# AnchorUWB.net
KiCad netlist of a schematic drawn in Altium Designer
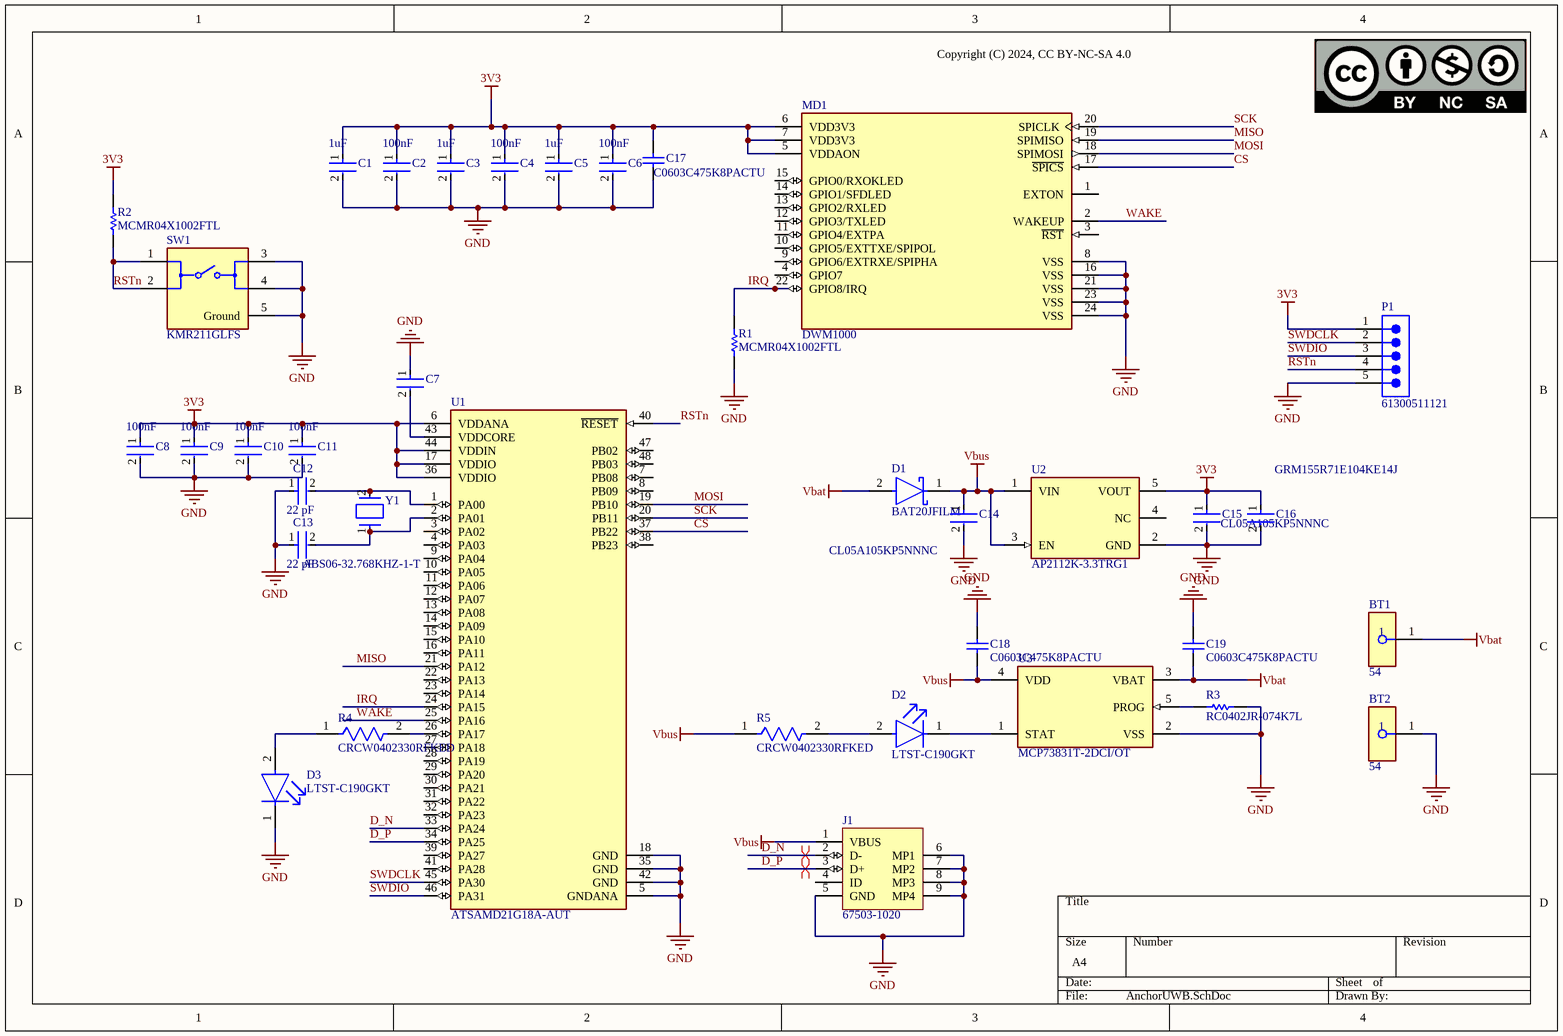
[diagram p0: AnchorUWB.SchDoc]

(export (version "E")
  (design (tool "Eeschema 10.0.6"))
  (components
    (comp (ref "BT1")
      (value "54")
      (footprint "FP-54-MFG")
      (description "BATTERY CONTACT CLP 18650 PC PIN")
      (libsource (lib "Altium Content Vault") (part "98815daf2f2c152b0c43f5ab9800df6"))
    )
    (comp (ref "BT2")
      (value "54")
      (footprint "FP-54-MFG")
      (description "BATTERY CONTACT CLP 18650 PC PIN")
      (libsource (lib "Altium Content Vault") (part "98815daf2f2c152b0c43f5ab9800df6"))
    )
    (comp (ref "C1")
      (value "CL05A105KP5NNNC")
      (footprint "FP-CL511-IPC_C")
      (description "Cap Ceramic 1uF 10V X5R ±10% SMD 0402 +85°C Paper T/R")
      (fields (field (name "CAPACITANCE") "1uF") (field (name "TOLERANCE") "10%"))
      (libsource (lib "Altium Content Vault") (part "b4654b650e69147ec39a6b967a45e02"))
    )
    (comp (ref "C2")
      (value "GRM155R71E104KE14J")
      (footprint "FP-GRM155-0_05-IPC_C")
      (description "Chip Multilayer Ceramic Capacitors for General Purpose, 0402, 0.10uF, X7R, 15%, 10%, 25V")
      (fields (field (name "CAPACITANCE") "100nF") (field (name "TOLERANCE") "10%"))
      (libsource (lib "Altium Content Vault") (part "02cd4be3c70576c341d710602a673aa"))
    )
    (comp (ref "C3")
      (value "CL05A105KP5NNNC")
      (footprint "FP-CL511-IPC_C")
      (description "Cap Ceramic 1uF 10V X5R ±10% SMD 0402 +85°C Paper T/R")
      (fields (field (name "CAPACITANCE") "1uF") (field (name "TOLERANCE") "10%"))
      (libsource (lib "Altium Content Vault") (part "b4654b650e69147ec39a6b967a45e02"))
    )
    (comp (ref "C4")
      (value "GRM155R71E104KE14J")
      (footprint "FP-GRM155-0_05-IPC_C")
      (description "Chip Multilayer Ceramic Capacitors for General Purpose, 0402, 0.10uF, X7R, 15%, 10%, 25V")
      (fields (field (name "CAPACITANCE") "100nF") (field (name "TOLERANCE") "10%"))
      (libsource (lib "Altium Content Vault") (part "02cd4be3c70576c341d710602a673aa"))
    )
    (comp (ref "C5")
      (value "CL05A105KP5NNNC")
      (footprint "FP-CL511-IPC_C")
      (description "Cap Ceramic 1uF 10V X5R ±10% SMD 0402 +85°C Paper T/R")
      (fields (field (name "CAPACITANCE") "1uF") (field (name "TOLERANCE") "10%"))
      (libsource (lib "Altium Content Vault") (part "b4654b650e69147ec39a6b967a45e02"))
    )
    (comp (ref "C6")
      (value "GRM155R71E104KE14J")
      (footprint "FP-GRM155-0_05-IPC_C")
      (description "Chip Multilayer Ceramic Capacitors for General Purpose, 0402, 0.10uF, X7R, 15%, 10%, 25V")
      (fields (field (name "CAPACITANCE") "100nF") (field (name "TOLERANCE") "10%"))
      (libsource (lib "Altium Content Vault") (part "02cd4be3c70576c341d710602a673aa"))
    )
    (comp (ref "C7")
      (value "CL05A105KP5NNNC")
      (footprint "FP-CL511-IPC_C")
      (description "Cap Ceramic 1uF 10V X5R ±10% SMD 0402 +85°C Paper T/R")
      (fields (field (name "TOLERANCE") "10%"))
      (libsource (lib "Altium Content Vault") (part "b4654b650e69147ec39a6b967a45e02"))
    )
    (comp (ref "C8")
      (value "GRM155R71E104KE14J")
      (footprint "FP-GRM155-0_05-IPC_C")
      (description "Chip Multilayer Ceramic Capacitors for General Purpose, 0402, 0.10uF, X7R, 15%, 10%, 25V")
      (fields (field (name "CAPACITANCE") "100nF") (field (name "TOLERANCE") "10%"))
      (libsource (lib "Altium Content Vault") (part "02cd4be3c70576c341d710602a673aa"))
    )
    (comp (ref "C9")
      (value "GRM155R71E104KE14J")
      (footprint "FP-GRM155-0_05-IPC_C")
      (description "Chip Multilayer Ceramic Capacitors for General Purpose, 0402, 0.10uF, X7R, 15%, 10%, 25V")
      (fields (field (name "CAPACITANCE") "100nF") (field (name "TOLERANCE") "10%"))
      (libsource (lib "Altium Content Vault") (part "02cd4be3c70576c341d710602a673aa"))
    )
    (comp (ref "C10")
      (value "GRM155R71E104KE14J")
      (footprint "FP-GRM155-0_05-IPC_C")
      (description "Chip Multilayer Ceramic Capacitors for General Purpose, 0402, 0.10uF, X7R, 15%, 10%, 25V")
      (fields (field (name "CAPACITANCE") "100nF") (field (name "TOLERANCE") "10%"))
      (libsource (lib "Altium Content Vault") (part "02cd4be3c70576c341d710602a673aa"))
    )
    (comp (ref "C11")
      (value "GRM155R71E104KE14J")
      (footprint "FP-GRM155-0_05-IPC_C")
      (description "Chip Multilayer Ceramic Capacitors for General Purpose, 0402, 0.10uF, X7R, 15%, 10%, 25V")
      (fields (field (name "CAPACITANCE") "100nF") (field (name "TOLERANCE") "10%"))
      (libsource (lib "Altium Content Vault") (part "02cd4be3c70576c341d710602a673aa"))
    )
    (comp (ref "C12")
      (value "C0402C220K5GACTU")
      (footprint "FP-C0402-BB-MFG")
      (description "CAP CER 22PF 50V 10% NP0 0402")
      (fields
        (field (name "OCTOPART") "https://octopart.com/c0402c220k5gactu-kemet-9144192")
        (field (name "CAPACITANCE") "22 pF")
        (field (name "TOLERANCE") "0.1")
      )
      (libsource (lib "Altium Content Vault") (part "b4654b650e69147ec39a6b967a45e02"))
    )
    (comp (ref "C13")
      (value "C0402C220K5GACTU")
      (footprint "FP-C0402-BB-MFG")
      (description "CAP CER 22PF 50V 10% NP0 0402")
      (fields
        (field (name "OCTOPART") "https://octopart.com/c0402c220k5gactu-kemet-9144192")
        (field (name "CAPACITANCE") "22 pF")
        (field (name "TOLERANCE") "0.1")
      )
      (libsource (lib "Altium Content Vault") (part "b4654b650e69147ec39a6b967a45e02"))
    )
    (comp (ref "C14")
      (value "CL05A105KP5NNNC")
      (footprint "FP-CL511-IPC_C")
      (description "Cap Ceramic 1uF 10V X5R ±10% SMD 0402 +85°C Paper T/R")
      (fields (field (name "TOLERANCE") "10%"))
      (libsource (lib "Altium Content Vault") (part "b4654b650e69147ec39a6b967a45e02"))
    )
    (comp (ref "C15")
      (value "CL05A105KP5NNNC")
      (footprint "FP-CL511-IPC_C")
      (description "Cap Ceramic 1uF 10V X5R ±10% SMD 0402 +85°C Paper T/R")
      (fields (field (name "TOLERANCE") "10%"))
      (libsource (lib "Altium Content Vault") (part "b4654b650e69147ec39a6b967a45e02"))
    )
    (comp (ref "C16")
      (value "GRM155R71E104KE14J")
      (footprint "FP-GRM155-0_05-IPC_C")
      (description "Chip Multilayer Ceramic Capacitors for General Purpose, 0402, 0.10uF, X7R, 15%, 10%, 25V")
      (fields (field (name "TOLERANCE") "10%"))
      (libsource (lib "Altium Content Vault") (part "02cd4be3c70576c341d710602a673aa"))
    )
    (comp (ref "C17")
      (value "C0603C475K8PACTU")
      (footprint "CAPC1608X87X35NL15T15")
      (fields (field (name "PART NUMBER") "C0603C475K8PACTU") (field (name "MANUFACTURER") "Kemet"))
      (libsource (lib "Altium Content Vault") (part "CAP"))
    )
    (comp (ref "C18")
      (value "C0603C475K8PACTU")
      (footprint "CAPC1608X87X35NL15T15")
      (fields (field (name "MANUFACTURER") "Kemet"))
      (libsource (lib "Altium Content Vault") (part "CAP"))
    )
    (comp (ref "C19")
      (value "C0603C475K8PACTU")
      (footprint "CAPC1608X87X35NL15T15")
      (fields (field (name "MANUFACTURER") "Kemet"))
      (libsource (lib "Altium Content Vault") (part "CAP"))
    )
    (comp (ref "D1")
      (value "BAT20JFILM")
      (footprint "FP-BAT20JFILM-MFG")
      (description "DIODE SCHOTTKY 23V 1A SOD323")
      (libsource (lib "Altium Content Vault") (part "fefb30dabb5d097ae2f038500735429"))
    )
    (comp (ref "D2")
      (value "LTST-C190GKT")
      (footprint "FP-LTST-C190GKT-MFG")
      (description "LED GREEN CLEAR CHIP SMD")
      (fields (field (name "VOLTAGE") "2V"))
      (libsource (lib "Altium Content Vault") (part "8706943c75ba83719d021d2fdc84c58"))
    )
    (comp (ref "D3")
      (value "LTST-C190GKT")
      (footprint "FP-LTST-C190GKT-MFG")
      (description "LED GREEN CLEAR CHIP SMD")
      (fields (field (name "VOLTAGE") "2V"))
      (libsource (lib "Altium Content Vault") (part "8706943c75ba83719d021d2fdc84c58"))
    )
    (comp (ref "J1")
      (value "67503-1020")
      (footprint "MOLX-67503-1020_V")
      (description "USB, MINI, SMD, RA KME04-USBMU03A01")
      (fields (field (name "MANUFACTURER") "Molex"))
      (libsource (lib "Altium Content Vault") (part "MOLX-67503-1020"))
    )
    (comp (ref "MD1")
      (value "DWM1000")
      (footprint "FP-DWM1000-MFG")
      (description "RX TXRX MODULE 802.15.4 CHIP SMD")
      (libsource (lib "Altium Content Vault") (part "f696d20320cfac42d99354fdc9dc59a"))
    )
    (comp (ref "P1")
      (value "61300511121")
      (footprint "61300511121")
      (libsource (lib "Altium Content Vault") (part "Header_Male_1R_05P"))
    )
    (comp (ref "R1")
      (value "MCMR04X1002FTL")
      (footprint "RESC1005X40X25NL05T10")
      (fields (field (name "MANUFACTURER") "Multicomp"))
      (libsource (lib "Altium Content Vault") (part "RES"))
    )
    (comp (ref "R2")
      (value "MCMR04X1002FTL")
      (footprint "RESC1005X40X25NL05T10")
      (fields (field (name "MANUFACTURER") "Multicomp"))
      (libsource (lib "Altium Content Vault") (part "RES"))
    )
    (comp (ref "R3")
      (value "RC0402JR-074K7L")
      (footprint "RESC1005X40X25LL05T10")
      (fields (field (name "MANUFACTURER") "Yageo / Phycomp"))
      (libsource (lib "Altium Content Vault") (part "RES"))
    )
    (comp (ref "R4")
      (value "CRCW0402330RFKED")
      (footprint "FP-CRCW0402-e3-MFG")
      (description "RES Thick Film, 330Ω, 1%, 0.063W, 100ppm/°C, 0402")
      (fields (field (name "TOLERANCE") "1%"))
      (libsource (lib "Altium Content Vault") (part "1029c3af85768c4190bb7ad29bc67b5"))
    )
    (comp (ref "R5")
      (value "CRCW0402330RFKED")
      (footprint "FP-CRCW0402-e3-MFG")
      (description "RES Thick Film, 330Ω, 1%, 0.063W, 100ppm/°C, 0402")
      (fields (field (name "TOLERANCE") "1%"))
      (libsource (lib "Altium Content Vault") (part "1029c3af85768c4190bb7ad29bc67b5"))
    )
    (comp (ref "SW1")
      (value "KMR211GLFS")
      (footprint "FP-KMR211GLFS-MFG")
      (description "SWITCH TACTILE SPST-NO 0.05A 32V")
      (libsource (lib "Altium Content Vault") (part "99988cc0f9d3d39bd794ae22da860e5"))
    )
    (comp (ref "U1")
      (value "ATSAMD21G18A-AUT")
      (footprint "FP-MC-MFG")
      (description "IC MCU 32BIT 256KB FLASH 48TQFP")
      (libsource (lib "Altium Content Vault") (part "cb504b5d9f62c9ff840dfafac9e9c83"))
    )
    (comp (ref "U2")
      (value "AP2112K-3.3TRG1")
      (footprint "FP-SOT25-IPC_A")
      (description "IC REG LINEAR 3.3V 600MA SOT25")
      (libsource (lib "Altium Content Vault") (part "c8ab751aee5229183125ab046a11caa"))
    )
    (comp (ref "U3")
      (value "MCP73831T-2DCI/OT")
      (footprint "FP-C04-091-OT-IPC_B")
      (description "IC CONTROLLR LI-ION 4.2V SOT23-5")
      (libsource (lib "Altium Content Vault") (part "61f5a3bb3429d9e0caadea342aa3b19"))
    )
    (comp (ref "Y1")
      (value "ABS06-32.768KHZ-1-T")
      (footprint "FP-ABS06-MFG")
      (description "CRYSTAL 32.7680KHZ 12.5PF SMD")
      (fields (field (name "TOLERANCE") "10ppm"))
      (libsource (lib "Altium Content Vault") (part "c23a69dc6c9e2f18f2079038eb95dd1"))
    )
  )
  (nets
    (net (code "1") (name "/CS") (class "Default")
      (node (ref "MD1") (pin "17") (pinfunction "~{SPICS}_17") (pintype "input"))
      (node (ref "U1") (pin "37") (pinfunction "PB22_37") (pintype "bidirectional"))
    )
    (net (code "2") (name "/D_N") (class "Default")
      (node (ref "J1") (pin "2") (pinfunction "D-_2") (pintype "bidirectional"))
      (node (ref "U1") (pin "33") (pinfunction "PA24_33") (pintype "bidirectional"))
    )
    (net (code "3") (name "/D_P") (class "Default")
      (node (ref "J1") (pin "3") (pinfunction "D+_3") (pintype "bidirectional"))
      (node (ref "U1") (pin "34") (pinfunction "PA25_34") (pintype "bidirectional"))
    )
    (net (code "4") (name "/IRQ") (class "Default")
      (node (ref "MD1") (pin "22") (pinfunction "GPIO8/IRQ_22") (pintype "bidirectional"))
      (node (ref "R1") (pin "2") (pinfunction "2_2") (pintype "passive"))
      (node (ref "U1") (pin "24") (pinfunction "PA15_24") (pintype "bidirectional"))
    )
    (net (code "5") (name "/MISO") (class "Default")
      (node (ref "MD1") (pin "19") (pinfunction "SPIMISO_19") (pintype "input"))
      (node (ref "U1") (pin "21") (pinfunction "PA12_21") (pintype "bidirectional"))
    )
    (net (code "6") (name "/MOSI") (class "Default")
      (node (ref "MD1") (pin "18") (pinfunction "SPIMOSI_18") (pintype "output"))
      (node (ref "U1") (pin "19") (pinfunction "PB10_19") (pintype "bidirectional"))
    )
    (net (code "7") (name "/RSTn") (class "Default")
      (node (ref "P1") (pin "4") (pinfunction "4_4") (pintype "passive"))
      (node (ref "R2") (pin "1") (pinfunction "1_1") (pintype "passive"))
      (node (ref "SW1") (pin "1") (pinfunction "1_1") (pintype "passive"))
      (node (ref "SW1") (pin "2") (pinfunction "2_2") (pintype "passive"))
      (node (ref "U1") (pin "40") (pinfunction "~{RESET}_40") (pintype "input"))
    )
    (net (code "8") (name "/SCK") (class "Default")
      (node (ref "MD1") (pin "20") (pinfunction "SPICLK_20") (pintype "input"))
      (node (ref "U1") (pin "20") (pinfunction "PB11_20") (pintype "bidirectional"))
    )
    (net (code "9") (name "/SWDCLK") (class "Default")
      (node (ref "P1") (pin "2") (pinfunction "2_2") (pintype "passive"))
      (node (ref "U1") (pin "45") (pinfunction "PA30_45") (pintype "bidirectional"))
    )
    (net (code "10") (name "/SWDIO") (class "Default")
      (node (ref "P1") (pin "3") (pinfunction "3_3") (pintype "passive"))
      (node (ref "U1") (pin "46") (pinfunction "PA31_46") (pintype "bidirectional"))
    )
    (net (code "11") (name "/WAKE") (class "Default")
      (node (ref "MD1") (pin "2") (pinfunction "WAKEUP_2") (pintype "passive"))
      (node (ref "U1") (pin "25") (pinfunction "PA16_25") (pintype "bidirectional"))
    )
    (net (code "12") (name "3V3") (class "Default")
      (node (ref "C1") (pin "1") (pinfunction "1_1") (pintype "passive"))
      (node (ref "C10") (pin "1") (pinfunction "1_1") (pintype "passive"))
      (node (ref "C11") (pin "1") (pinfunction "1_1") (pintype "passive"))
      (node (ref "C15") (pin "1") (pinfunction "1_1") (pintype "passive"))
      (node (ref "C16") (pin "1") (pinfunction "1_1") (pintype "passive"))
      (node (ref "C17") (pin "2") (pinfunction "2_2") (pintype "passive"))
      (node (ref "C2") (pin "1") (pinfunction "1_1") (pintype "passive"))
      (node (ref "C3") (pin "1") (pinfunction "1_1") (pintype "passive"))
      (node (ref "C4") (pin "1") (pinfunction "1_1") (pintype "passive"))
      (node (ref "C5") (pin "1") (pinfunction "1_1") (pintype "passive"))
      (node (ref "C6") (pin "1") (pinfunction "1_1") (pintype "passive"))
      (node (ref "C8") (pin "1") (pinfunction "1_1") (pintype "passive"))
      (node (ref "C9") (pin "1") (pinfunction "1_1") (pintype "passive"))
      (node (ref "MD1") (pin "5") (pinfunction "VDDAON_5") (pintype "power_in"))
      (node (ref "MD1") (pin "6") (pinfunction "VDD3V3_6") (pintype "power_in"))
      (node (ref "MD1") (pin "7") (pinfunction "VDD3V3_7") (pintype "power_in"))
      (node (ref "P1") (pin "1") (pinfunction "1_1") (pintype "passive"))
      (node (ref "R2") (pin "2") (pinfunction "2_2") (pintype "passive"))
      (node (ref "U1") (pin "17") (pinfunction "VDDIO_17") (pintype "power_in"))
      (node (ref "U1") (pin "36") (pinfunction "VDDIO_36") (pintype "power_in"))
      (node (ref "U1") (pin "44") (pinfunction "VDDIN_44") (pintype "power_in"))
      (node (ref "U1") (pin "6") (pinfunction "VDDANA_6") (pintype "power_in"))
      (node (ref "U2") (pin "5") (pinfunction "VOUT_5") (pintype "power_in"))
    )
    (net (code "13") (name "GND") (class "Default")
      (node (ref "BT2") (pin "1") (pinfunction "1_1") (pintype "power_in"))
      (node (ref "C1") (pin "2") (pinfunction "2_2") (pintype "passive"))
      (node (ref "C10") (pin "2") (pinfunction "2_2") (pintype "passive"))
      (node (ref "C11") (pin "2") (pinfunction "2_2") (pintype "passive"))
      (node (ref "C12") (pin "1") (pinfunction "1_1") (pintype "passive"))
      (node (ref "C13") (pin "1") (pinfunction "1_1") (pintype "passive"))
      (node (ref "C14") (pin "2") (pinfunction "2_2") (pintype "passive"))
      (node (ref "C15") (pin "2") (pinfunction "2_2") (pintype "passive"))
      (node (ref "C16") (pin "2") (pinfunction "2_2") (pintype "passive"))
      (node (ref "C17") (pin "1") (pinfunction "1_1") (pintype "passive"))
      (node (ref "C18") (pin "2") (pinfunction "2_2") (pintype "passive"))
      (node (ref "C19") (pin "2") (pinfunction "2_2") (pintype "passive"))
      (node (ref "C2") (pin "2") (pinfunction "2_2") (pintype "passive"))
      (node (ref "C3") (pin "2") (pinfunction "2_2") (pintype "passive"))
      (node (ref "C4") (pin "2") (pinfunction "2_2") (pintype "passive"))
      (node (ref "C5") (pin "2") (pinfunction "2_2") (pintype "passive"))
      (node (ref "C6") (pin "2") (pinfunction "2_2") (pintype "passive"))
      (node (ref "C7") (pin "1") (pinfunction "1_1") (pintype "passive"))
      (node (ref "C8") (pin "2") (pinfunction "2_2") (pintype "passive"))
      (node (ref "C9") (pin "2") (pinfunction "2_2") (pintype "passive"))
      (node (ref "D3") (pin "1") (pinfunction "C_1") (pintype "passive"))
      (node (ref "J1") (pin "5") (pinfunction "GND_5") (pintype "power_in"))
      (node (ref "J1") (pin "6") (pinfunction "MP1_6") (pintype "passive"))
      (node (ref "J1") (pin "7") (pinfunction "MP2_7") (pintype "passive"))
      (node (ref "J1") (pin "8") (pinfunction "MP3_8") (pintype "passive"))
      (node (ref "J1") (pin "9") (pinfunction "MP4_9") (pintype "passive"))
      (node (ref "MD1") (pin "16") (pinfunction "VSS_16") (pintype "power_in"))
      (node (ref "MD1") (pin "21") (pinfunction "VSS_21") (pintype "power_in"))
      (node (ref "MD1") (pin "23") (pinfunction "VSS_23") (pintype "power_in"))
      (node (ref "MD1") (pin "24") (pinfunction "VSS_24") (pintype "power_in"))
      (node (ref "MD1") (pin "8") (pinfunction "VSS_8") (pintype "power_in"))
      (node (ref "P1") (pin "5") (pinfunction "5_5") (pintype "passive"))
      (node (ref "R1") (pin "1") (pinfunction "1_1") (pintype "passive"))
      (node (ref "R3") (pin "2") (pinfunction "2_2") (pintype "passive"))
      (node (ref "SW1") (pin "3") (pinfunction "3_3") (pintype "passive"))
      (node (ref "SW1") (pin "4") (pinfunction "4_4") (pintype "passive"))
      (node (ref "SW1") (pin "5") (pinfunction "Ground_5") (pintype "power_in"))
      (node (ref "U1") (pin "18") (pinfunction "GND_18") (pintype "power_in"))
      (node (ref "U1") (pin "35") (pinfunction "GND_35") (pintype "power_in"))
      (node (ref "U1") (pin "42") (pinfunction "GND_42") (pintype "power_in"))
      (node (ref "U1") (pin "5") (pinfunction "GNDANA_5") (pintype "power_in"))
      (node (ref "U2") (pin "2") (pinfunction "GND_2") (pintype "power_in"))
      (node (ref "U3") (pin "2") (pinfunction "VSS_2") (pintype "power_in"))
    )
    (net (code "14") (name "Net-(D2-A)") (class "Default")
      (node (ref "D2") (pin "2") (pinfunction "A_2") (pintype "passive"))
      (node (ref "R5") (pin "2") (pinfunction "2_2") (pintype "passive"))
    )
    (net (code "15") (name "Net-(D2-C)") (class "Default")
      (node (ref "D2") (pin "1") (pinfunction "C_1") (pintype "passive"))
      (node (ref "U3") (pin "1") (pinfunction "STAT_1") (pintype "passive"))
    )
    (net (code "16") (name "Net-(D3-A)") (class "Default")
      (node (ref "D3") (pin "2") (pinfunction "A_2") (pintype "passive"))
      (node (ref "R4") (pin "1") (pinfunction "1_1") (pintype "passive"))
    )
    (net (code "17") (name "Net-(U1-PA00)") (class "Default")
      (node (ref "C12") (pin "2") (pinfunction "2_2") (pintype "passive"))
      (node (ref "U1") (pin "1") (pinfunction "PA00_1") (pintype "bidirectional"))
      (node (ref "Y1") (pin "2") (pinfunction "2_2") (pintype "passive"))
    )
    (net (code "18") (name "Net-(U1-PA01)") (class "Default")
      (node (ref "C13") (pin "2") (pinfunction "2_2") (pintype "passive"))
      (node (ref "U1") (pin "2") (pinfunction "PA01_2") (pintype "bidirectional"))
      (node (ref "Y1") (pin "1") (pinfunction "1_1") (pintype "passive"))
    )
    (net (code "19") (name "Net-(U1-PA17)") (class "Default")
      (node (ref "R4") (pin "2") (pinfunction "2_2") (pintype "passive"))
      (node (ref "U1") (pin "26") (pinfunction "PA17_26") (pintype "bidirectional"))
    )
    (net (code "20") (name "Net-(U1-VDDCORE)") (class "Default")
      (node (ref "C7") (pin "2") (pinfunction "2_2") (pintype "passive"))
      (node (ref "U1") (pin "43") (pinfunction "VDDCORE_43") (pintype "power_in"))
    )
    (net (code "21") (name "Net-(U3-PROG)") (class "Default")
      (node (ref "R3") (pin "1") (pinfunction "1_1") (pintype "passive"))
      (node (ref "U3") (pin "5") (pinfunction "PROG_5") (pintype "input"))
    )
    (net (code "22") (name "Vbat") (class "Default")
      (node (ref "BT1") (pin "1") (pinfunction "1_1") (pintype "power_in"))
      (node (ref "C19") (pin "1") (pinfunction "1_1") (pintype "passive"))
      (node (ref "D1") (pin "2") (pinfunction "A_2") (pintype "passive"))
      (node (ref "U3") (pin "3") (pinfunction "VBAT_3") (pintype "power_in"))
    )
    (net (code "23") (name "Vbus") (class "Default")
      (node (ref "C14") (pin "1") (pinfunction "1_1") (pintype "passive"))
      (node (ref "C18") (pin "1") (pinfunction "1_1") (pintype "passive"))
      (node (ref "D1") (pin "1") (pinfunction "K_1") (pintype "passive"))
      (node (ref "J1") (pin "1") (pinfunction "VBUS_1") (pintype "power_in"))
      (node (ref "R5") (pin "1") (pinfunction "1_1") (pintype "passive"))
      (node (ref "U2") (pin "1") (pinfunction "VIN_1") (pintype "power_in"))
      (node (ref "U2") (pin "3") (pinfunction "EN_3") (pintype "input"))
      (node (ref "U3") (pin "4") (pinfunction "VDD_4") (pintype "open_emitter"))
    )
    (net (code "24") (name "unconnected-(J1-ID-Pad4)") (class "Default")
      (node (ref "J1") (pin "4") (pinfunction "ID_4") (pintype "passive"))
    )
    (net (code "25") (name "unconnected-(MD1-EXTON-Pad1)") (class "Default")
      (node (ref "MD1") (pin "1") (pinfunction "EXTON_1") (pintype "passive"))
    )
    (net (code "26") (name "unconnected-(MD1-GPIO0{slash}RXOKLED-Pad15)") (class "Default")
      (node (ref "MD1") (pin "15") (pinfunction "GPIO0/RXOKLED_15") (pintype "bidirectional"))
    )
    (net (code "27") (name "unconnected-(MD1-GPIO1{slash}SFDLED-Pad14)") (class "Default")
      (node (ref "MD1") (pin "14") (pinfunction "GPIO1/SFDLED_14") (pintype "bidirectional"))
    )
    (net (code "28") (name "unconnected-(MD1-GPIO2{slash}RXLED-Pad13)") (class "Default")
      (node (ref "MD1") (pin "13") (pinfunction "GPIO2/RXLED_13") (pintype "bidirectional"))
    )
    (net (code "29") (name "unconnected-(MD1-GPIO3{slash}TXLED-Pad12)") (class "Default")
      (node (ref "MD1") (pin "12") (pinfunction "GPIO3/TXLED_12") (pintype "bidirectional"))
    )
    (net (code "30") (name "unconnected-(MD1-GPIO4{slash}EXTPA-Pad11)") (class "Default")
      (node (ref "MD1") (pin "11") (pinfunction "GPIO4/EXTPA_11") (pintype "bidirectional"))
    )
    (net (code "31") (name "unconnected-(MD1-GPIO5{slash}EXTTXE{slash}SPIPOL-Pad10)") (class "Default")
      (node (ref "MD1") (pin "10") (pinfunction "GPIO5/EXTTXE/SPIPOL_10") (pintype "bidirectional"))
    )
    (net (code "32") (name "unconnected-(MD1-GPIO6{slash}EXTRXE{slash}SPIPHA-Pad9)") (class "Default")
      (node (ref "MD1") (pin "9") (pinfunction "GPIO6/EXTRXE/SPIPHA_9") (pintype "bidirectional"))
    )
    (net (code "33") (name "unconnected-(MD1-GPIO7-Pad4)") (class "Default")
      (node (ref "MD1") (pin "4") (pinfunction "GPIO7_4") (pintype "bidirectional"))
    )
    (net (code "34") (name "unconnected-(MD1-~{RST}-Pad3)") (class "Default")
      (node (ref "MD1") (pin "3") (pinfunction "~{RST}_3") (pintype "input"))
    )
    (net (code "35") (name "unconnected-(U1-PA02-Pad3)") (class "Default")
      (node (ref "U1") (pin "3") (pinfunction "PA02_3") (pintype "bidirectional"))
    )
    (net (code "36") (name "unconnected-(U1-PA03-Pad4)") (class "Default")
      (node (ref "U1") (pin "4") (pinfunction "PA03_4") (pintype "bidirectional"))
    )
    (net (code "37") (name "unconnected-(U1-PA04-Pad9)") (class "Default")
      (node (ref "U1") (pin "9") (pinfunction "PA04_9") (pintype "bidirectional"))
    )
    (net (code "38") (name "unconnected-(U1-PA05-Pad10)") (class "Default")
      (node (ref "U1") (pin "10") (pinfunction "PA05_10") (pintype "bidirectional"))
    )
    (net (code "39") (name "unconnected-(U1-PA06-Pad11)") (class "Default")
      (node (ref "U1") (pin "11") (pinfunction "PA06_11") (pintype "bidirectional"))
    )
    (net (code "40") (name "unconnected-(U1-PA07-Pad12)") (class "Default")
      (node (ref "U1") (pin "12") (pinfunction "PA07_12") (pintype "bidirectional"))
    )
    (net (code "41") (name "unconnected-(U1-PA08-Pad13)") (class "Default")
      (node (ref "U1") (pin "13") (pinfunction "PA08_13") (pintype "bidirectional"))
    )
    (net (code "42") (name "unconnected-(U1-PA09-Pad14)") (class "Default")
      (node (ref "U1") (pin "14") (pinfunction "PA09_14") (pintype "bidirectional"))
    )
    (net (code "43") (name "unconnected-(U1-PA10-Pad15)") (class "Default")
      (node (ref "U1") (pin "15") (pinfunction "PA10_15") (pintype "bidirectional"))
    )
    (net (code "44") (name "unconnected-(U1-PA11-Pad16)") (class "Default")
      (node (ref "U1") (pin "16") (pinfunction "PA11_16") (pintype "bidirectional"))
    )
    (net (code "45") (name "unconnected-(U1-PA13-Pad22)") (class "Default")
      (node (ref "U1") (pin "22") (pinfunction "PA13_22") (pintype "bidirectional"))
    )
    (net (code "46") (name "unconnected-(U1-PA14-Pad23)") (class "Default")
      (node (ref "U1") (pin "23") (pinfunction "PA14_23") (pintype "bidirectional"))
    )
    (net (code "47") (name "unconnected-(U1-PA18-Pad27)") (class "Default")
      (node (ref "U1") (pin "27") (pinfunction "PA18_27") (pintype "bidirectional"))
    )
    (net (code "48") (name "unconnected-(U1-PA19-Pad28)") (class "Default")
      (node (ref "U1") (pin "28") (pinfunction "PA19_28") (pintype "bidirectional"))
    )
    (net (code "49") (name "unconnected-(U1-PA20-Pad29)") (class "Default")
      (node (ref "U1") (pin "29") (pinfunction "PA20_29") (pintype "bidirectional"))
    )
    (net (code "50") (name "unconnected-(U1-PA21-Pad30)") (class "Default")
      (node (ref "U1") (pin "30") (pinfunction "PA21_30") (pintype "bidirectional"))
    )
    (net (code "51") (name "unconnected-(U1-PA22-Pad31)") (class "Default")
      (node (ref "U1") (pin "31") (pinfunction "PA22_31") (pintype "bidirectional"))
    )
    (net (code "52") (name "unconnected-(U1-PA23-Pad32)") (class "Default")
      (node (ref "U1") (pin "32") (pinfunction "PA23_32") (pintype "bidirectional"))
    )
    (net (code "53") (name "unconnected-(U1-PA27-Pad39)") (class "Default")
      (node (ref "U1") (pin "39") (pinfunction "PA27_39") (pintype "bidirectional"))
    )
    (net (code "54") (name "unconnected-(U1-PA28-Pad41)") (class "Default")
      (node (ref "U1") (pin "41") (pinfunction "PA28_41") (pintype "bidirectional"))
    )
    (net (code "55") (name "unconnected-(U1-PB02-Pad47)") (class "Default")
      (node (ref "U1") (pin "47") (pinfunction "PB02_47") (pintype "bidirectional"))
    )
    (net (code "56") (name "unconnected-(U1-PB03-Pad48)") (class "Default")
      (node (ref "U1") (pin "48") (pinfunction "PB03_48") (pintype "bidirectional"))
    )
    (net (code "57") (name "unconnected-(U1-PB08-Pad7)") (class "Default")
      (node (ref "U1") (pin "7") (pinfunction "PB08_7") (pintype "bidirectional"))
    )
    (net (code "58") (name "unconnected-(U1-PB09-Pad8)") (class "Default")
      (node (ref "U1") (pin "8") (pinfunction "PB09_8") (pintype "bidirectional"))
    )
    (net (code "59") (name "unconnected-(U1-PB23-Pad38)") (class "Default")
      (node (ref "U1") (pin "38") (pinfunction "PB23_38") (pintype "bidirectional"))
    )
    (net (code "60") (name "unconnected-(U2-NC-Pad4)") (class "Default")
      (node (ref "U2") (pin "4") (pinfunction "NC_4") (pintype "passive"))
    )
  )
)
